# Dist.net
KiCad netlist of a schematic drawn in EAGLE
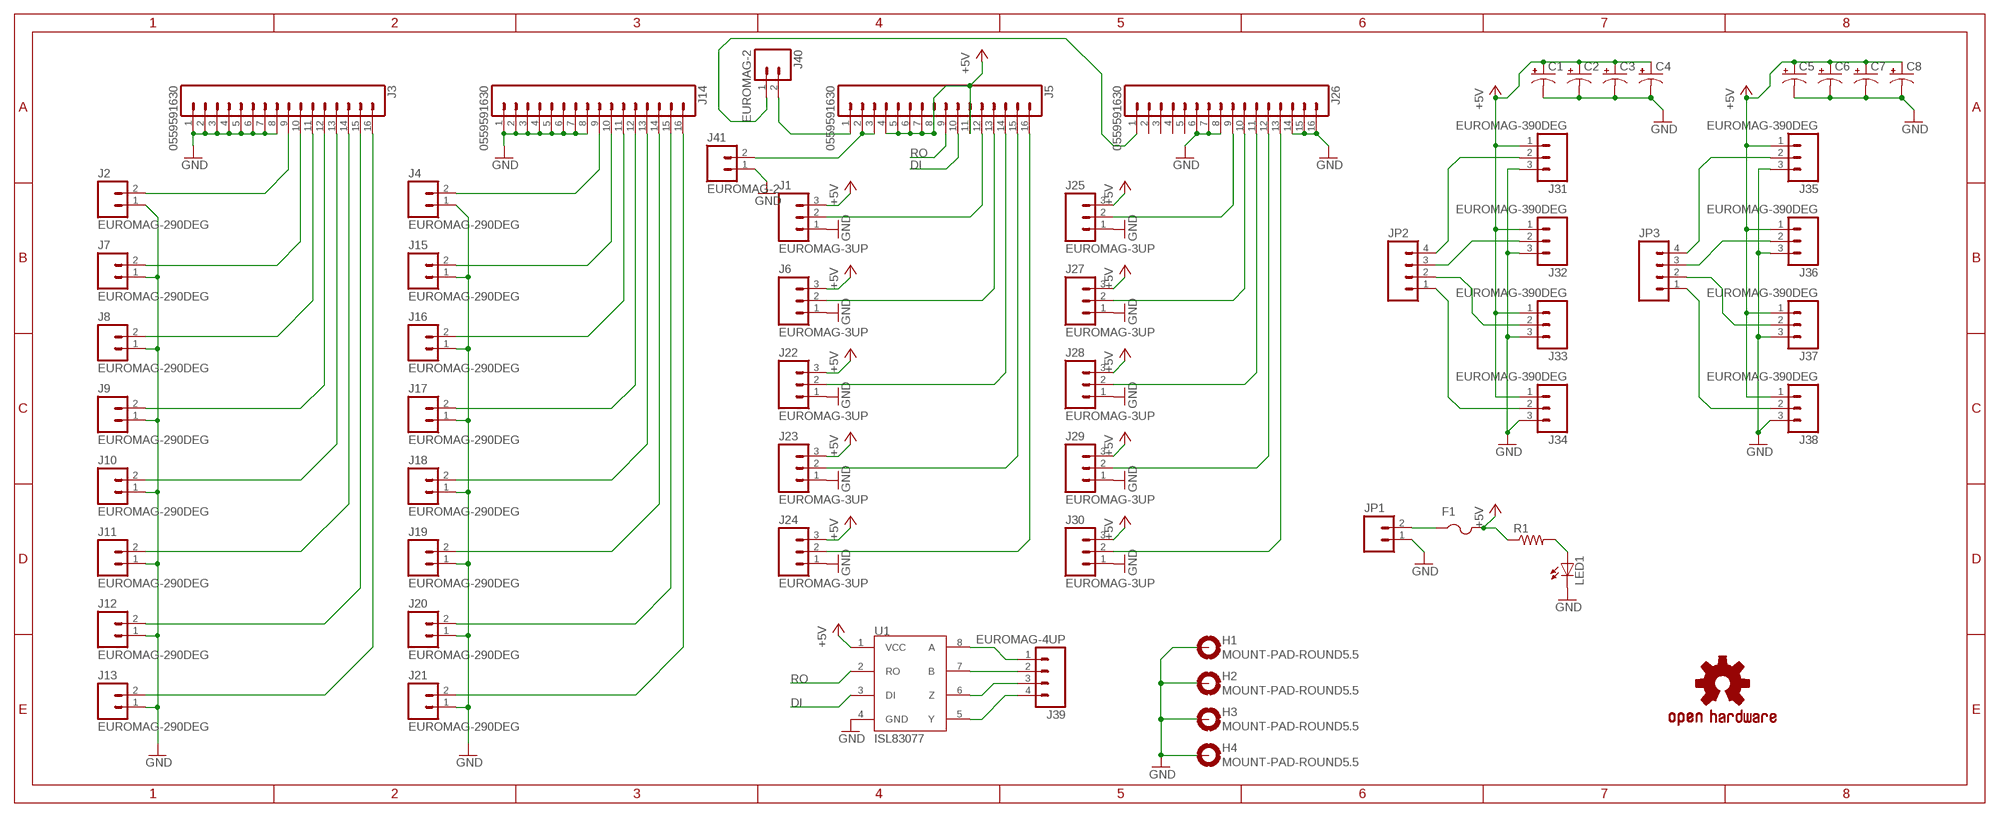
[diagram p0: schematic, sheet 1]

(export (version "E")
  (design (tool "Eeschema 10.0.6"))
  (components
    (comp (ref "C1")
      (value "CAP_POL3528")
      (footprint "eagle-import:EIA3528")
      (libsource (lib "eagle-import") (part "CAP_POL3528"))
    )
    (comp (ref "C2")
      (value "CAP_POL3528")
      (footprint "eagle-import:EIA3528")
      (libsource (lib "eagle-import") (part "CAP_POL3528"))
    )
    (comp (ref "C3")
      (value "CAP_POL3528")
      (footprint "eagle-import:EIA3528")
      (libsource (lib "eagle-import") (part "CAP_POL3528"))
    )
    (comp (ref "C4")
      (value "CAP_POL3528")
      (footprint "eagle-import:EIA3528")
      (libsource (lib "eagle-import") (part "CAP_POL3528"))
    )
    (comp (ref "C5")
      (value "CAP_POL3528")
      (footprint "eagle-import:EIA3528")
      (libsource (lib "eagle-import") (part "CAP_POL3528"))
    )
    (comp (ref "C6")
      (value "CAP_POL3528")
      (footprint "eagle-import:EIA3528")
      (libsource (lib "eagle-import") (part "CAP_POL3528"))
    )
    (comp (ref "C7")
      (value "CAP_POL3528")
      (footprint "eagle-import:EIA3528")
      (libsource (lib "eagle-import") (part "CAP_POL3528"))
    )
    (comp (ref "C8")
      (value "CAP_POL3528")
      (footprint "eagle-import:EIA3528")
      (libsource (lib "eagle-import") (part "CAP_POL3528"))
    )
    (comp (ref "F1")
      (value "PTCFUSE-1812")
      (footprint "eagle-import:1812")
      (libsource (lib "eagle-import") (part "PTCFUSE-1812"))
    )
    (comp (ref "H1")
      (value "MOUNT-PAD-ROUND5.5")
      (footprint "eagle-import:5,5-PAD")
      (libsource (lib "eagle-import") (part "MOUNT-PAD-ROUND5.5"))
    )
    (comp (ref "H2")
      (value "MOUNT-PAD-ROUND5.5")
      (footprint "eagle-import:5,5-PAD")
      (libsource (lib "eagle-import") (part "MOUNT-PAD-ROUND5.5"))
    )
    (comp (ref "H3")
      (value "MOUNT-PAD-ROUND5.5")
      (footprint "eagle-import:5,5-PAD")
      (libsource (lib "eagle-import") (part "MOUNT-PAD-ROUND5.5"))
    )
    (comp (ref "H4")
      (value "MOUNT-PAD-ROUND5.5")
      (footprint "eagle-import:5,5-PAD")
      (libsource (lib "eagle-import") (part "MOUNT-PAD-ROUND5.5"))
    )
    (comp (ref "J1")
      (value "EUROMAG-3UP")
      (footprint "eagle-import:M3-UP")
      (libsource (lib "eagle-import") (part "EUROMAG-3UP"))
    )
    (comp (ref "J2")
      (value "EUROMAG-290DEG")
      (footprint "eagle-import:M2")
      (libsource (lib "eagle-import") (part "EUROMAG-290DEG"))
    )
    (comp (ref "J3")
      (value "0559591630")
      (footprint "eagle-import:0559591630")
      (libsource (lib "eagle-import") (part "0559591630"))
    )
    (comp (ref "J4")
      (value "EUROMAG-290DEG")
      (footprint "eagle-import:M2")
      (libsource (lib "eagle-import") (part "EUROMAG-290DEG"))
    )
    (comp (ref "J5")
      (value "0559591630")
      (footprint "eagle-import:0559591630")
      (libsource (lib "eagle-import") (part "0559591630"))
    )
    (comp (ref "J6")
      (value "EUROMAG-3UP")
      (footprint "eagle-import:M3-UP")
      (libsource (lib "eagle-import") (part "EUROMAG-3UP"))
    )
    (comp (ref "J7")
      (value "EUROMAG-290DEG")
      (footprint "eagle-import:M2")
      (libsource (lib "eagle-import") (part "EUROMAG-290DEG"))
    )
    (comp (ref "J8")
      (value "EUROMAG-290DEG")
      (footprint "eagle-import:M2")
      (libsource (lib "eagle-import") (part "EUROMAG-290DEG"))
    )
    (comp (ref "J9")
      (value "EUROMAG-290DEG")
      (footprint "eagle-import:M2")
      (libsource (lib "eagle-import") (part "EUROMAG-290DEG"))
    )
    (comp (ref "J10")
      (value "EUROMAG-290DEG")
      (footprint "eagle-import:M2")
      (libsource (lib "eagle-import") (part "EUROMAG-290DEG"))
    )
    (comp (ref "J11")
      (value "EUROMAG-290DEG")
      (footprint "eagle-import:M2")
      (libsource (lib "eagle-import") (part "EUROMAG-290DEG"))
    )
    (comp (ref "J12")
      (value "EUROMAG-290DEG")
      (footprint "eagle-import:M2")
      (libsource (lib "eagle-import") (part "EUROMAG-290DEG"))
    )
    (comp (ref "J13")
      (value "EUROMAG-290DEG")
      (footprint "eagle-import:M2")
      (libsource (lib "eagle-import") (part "EUROMAG-290DEG"))
    )
    (comp (ref "J14")
      (value "0559591630")
      (footprint "eagle-import:0559591630")
      (libsource (lib "eagle-import") (part "0559591630"))
    )
    (comp (ref "J15")
      (value "EUROMAG-290DEG")
      (footprint "eagle-import:M2")
      (libsource (lib "eagle-import") (part "EUROMAG-290DEG"))
    )
    (comp (ref "J16")
      (value "EUROMAG-290DEG")
      (footprint "eagle-import:M2")
      (libsource (lib "eagle-import") (part "EUROMAG-290DEG"))
    )
    (comp (ref "J17")
      (value "EUROMAG-290DEG")
      (footprint "eagle-import:M2")
      (libsource (lib "eagle-import") (part "EUROMAG-290DEG"))
    )
    (comp (ref "J18")
      (value "EUROMAG-290DEG")
      (footprint "eagle-import:M2")
      (libsource (lib "eagle-import") (part "EUROMAG-290DEG"))
    )
    (comp (ref "J19")
      (value "EUROMAG-290DEG")
      (footprint "eagle-import:M2")
      (libsource (lib "eagle-import") (part "EUROMAG-290DEG"))
    )
    (comp (ref "J20")
      (value "EUROMAG-290DEG")
      (footprint "eagle-import:M2")
      (libsource (lib "eagle-import") (part "EUROMAG-290DEG"))
    )
    (comp (ref "J21")
      (value "EUROMAG-290DEG")
      (footprint "eagle-import:M2")
      (libsource (lib "eagle-import") (part "EUROMAG-290DEG"))
    )
    (comp (ref "J22")
      (value "EUROMAG-3UP")
      (footprint "eagle-import:M3-UP")
      (libsource (lib "eagle-import") (part "EUROMAG-3UP"))
    )
    (comp (ref "J23")
      (value "EUROMAG-3UP")
      (footprint "eagle-import:M3-UP")
      (libsource (lib "eagle-import") (part "EUROMAG-3UP"))
    )
    (comp (ref "J24")
      (value "EUROMAG-3UP")
      (footprint "eagle-import:M3-UP")
      (libsource (lib "eagle-import") (part "EUROMAG-3UP"))
    )
    (comp (ref "J25")
      (value "EUROMAG-3UP")
      (footprint "eagle-import:M3-UP")
      (libsource (lib "eagle-import") (part "EUROMAG-3UP"))
    )
    (comp (ref "J26")
      (value "0559591630")
      (footprint "eagle-import:0559591630")
      (libsource (lib "eagle-import") (part "0559591630"))
    )
    (comp (ref "J27")
      (value "EUROMAG-3UP")
      (footprint "eagle-import:M3-UP")
      (libsource (lib "eagle-import") (part "EUROMAG-3UP"))
    )
    (comp (ref "J28")
      (value "EUROMAG-3UP")
      (footprint "eagle-import:M3-UP")
      (libsource (lib "eagle-import") (part "EUROMAG-3UP"))
    )
    (comp (ref "J29")
      (value "EUROMAG-3UP")
      (footprint "eagle-import:M3-UP")
      (libsource (lib "eagle-import") (part "EUROMAG-3UP"))
    )
    (comp (ref "J30")
      (value "EUROMAG-3UP")
      (footprint "eagle-import:M3-UP")
      (libsource (lib "eagle-import") (part "EUROMAG-3UP"))
    )
    (comp (ref "J31")
      (value "EUROMAG-390DEG")
      (footprint "eagle-import:M3")
      (libsource (lib "eagle-import") (part "EUROMAG-390DEG"))
    )
    (comp (ref "J32")
      (value "EUROMAG-390DEG")
      (footprint "eagle-import:M3")
      (libsource (lib "eagle-import") (part "EUROMAG-390DEG"))
    )
    (comp (ref "J33")
      (value "EUROMAG-390DEG")
      (footprint "eagle-import:M3")
      (libsource (lib "eagle-import") (part "EUROMAG-390DEG"))
    )
    (comp (ref "J34")
      (value "EUROMAG-390DEG")
      (footprint "eagle-import:M3")
      (libsource (lib "eagle-import") (part "EUROMAG-390DEG"))
    )
    (comp (ref "J35")
      (value "EUROMAG-390DEG")
      (footprint "eagle-import:M3")
      (libsource (lib "eagle-import") (part "EUROMAG-390DEG"))
    )
    (comp (ref "J36")
      (value "EUROMAG-390DEG")
      (footprint "eagle-import:M3")
      (libsource (lib "eagle-import") (part "EUROMAG-390DEG"))
    )
    (comp (ref "J37")
      (value "EUROMAG-390DEG")
      (footprint "eagle-import:M3")
      (libsource (lib "eagle-import") (part "EUROMAG-390DEG"))
    )
    (comp (ref "J38")
      (value "EUROMAG-390DEG")
      (footprint "eagle-import:M3")
      (libsource (lib "eagle-import") (part "EUROMAG-390DEG"))
    )
    (comp (ref "J39")
      (value "EUROMAG-4UP")
      (footprint "eagle-import:M4-90")
      (libsource (lib "eagle-import") (part "EUROMAG-4UP"))
    )
    (comp (ref "J40")
      (value "EUROMAG-2")
      (footprint "eagle-import:M2-UP")
      (libsource (lib "eagle-import") (part "EUROMAG-2"))
    )
    (comp (ref "J41")
      (value "EUROMAG-2")
      (footprint "eagle-import:M2-UP")
      (libsource (lib "eagle-import") (part "EUROMAG-2"))
    )
    (comp (ref "JP1")
      (value "M02POLAR_LOCK")
      (footprint "eagle-import:MOLEX-1X2_LOCK")
      (libsource (lib "eagle-import") (part "M02POLAR_LOCK"))
    )
    (comp (ref "JP2")
      (value "M04POLAR_LOCK")
      (footprint "eagle-import:MOLEX-1X4_LOCK")
      (libsource (lib "eagle-import") (part "M04POLAR_LOCK"))
    )
    (comp (ref "JP3")
      (value "M04POLAR_LOCK")
      (footprint "eagle-import:MOLEX-1X4_LOCK")
      (libsource (lib "eagle-import") (part "M04POLAR_LOCK"))
    )
    (comp (ref "LED1")
      (value "LEDCHIPLED_0805")
      (footprint "eagle-import:CHIPLED_0805")
      (libsource (lib "eagle-import") (part "LEDCHIPLED_0805"))
    )
    (comp (ref "R1")
      (value "R-US_R0805")
      (footprint "eagle-import:R0805")
      (libsource (lib "eagle-import") (part "R-US_R0805"))
    )
    (comp (ref "U$1")
      (value "OSHW-LOGOL")
      (footprint "eagle-import:OSHW-LOGO-L")
      (libsource (lib "eagle-import") (part "OSHW-LOGOL"))
    )
    (comp (ref "U1")
      (value "ISL83077")
      (footprint "eagle-import:SO08")
      (libsource (lib "eagle-import") (part "ISL83077"))
    )
  )
  (nets
    (net (code "1") (name "+5V") (class "Default")
      (node (ref "C1") (pin "A") (pinfunction "+_A") (pintype "passive"))
      (node (ref "C2") (pin "A") (pinfunction "+_A") (pintype "passive"))
      (node (ref "C3") (pin "A") (pinfunction "+_A") (pintype "passive"))
      (node (ref "C4") (pin "A") (pinfunction "+_A") (pintype "passive"))
      (node (ref "C5") (pin "A") (pinfunction "+_A") (pintype "passive"))
      (node (ref "C6") (pin "A") (pinfunction "+_A") (pintype "passive"))
      (node (ref "C7") (pin "A") (pinfunction "+_A") (pintype "passive"))
      (node (ref "C8") (pin "A") (pinfunction "+_A") (pintype "passive"))
      (node (ref "F1") (pin "2") (pinfunction "2_2") (pintype "passive"))
      (node (ref "J1") (pin "3") (pinfunction "3_3") (pintype "passive"))
      (node (ref "J22") (pin "3") (pinfunction "3_3") (pintype "passive"))
      (node (ref "J23") (pin "3") (pinfunction "3_3") (pintype "passive"))
      (node (ref "J24") (pin "3") (pinfunction "3_3") (pintype "passive"))
      (node (ref "J25") (pin "3") (pinfunction "3_3") (pintype "passive"))
      (node (ref "J27") (pin "3") (pinfunction "3_3") (pintype "passive"))
      (node (ref "J28") (pin "3") (pinfunction "3_3") (pintype "passive"))
      (node (ref "J29") (pin "3") (pinfunction "3_3") (pintype "passive"))
      (node (ref "J30") (pin "3") (pinfunction "3_3") (pintype "passive"))
      (node (ref "J31") (pin "1") (pinfunction "1_1") (pintype "passive"))
      (node (ref "J32") (pin "1") (pinfunction "1_1") (pintype "passive"))
      (node (ref "J33") (pin "1") (pinfunction "1_1") (pintype "passive"))
      (node (ref "J34") (pin "1") (pinfunction "1_1") (pintype "passive"))
      (node (ref "J35") (pin "1") (pinfunction "1_1") (pintype "passive"))
      (node (ref "J36") (pin "1") (pinfunction "1_1") (pintype "passive"))
      (node (ref "J37") (pin "1") (pinfunction "1_1") (pintype "passive"))
      (node (ref "J38") (pin "1") (pinfunction "1_1") (pintype "passive"))
      (node (ref "J5") (pin "11") (pinfunction "11_11") (pintype "passive"))
      (node (ref "J5") (pin "4") (pinfunction "4_4") (pintype "passive"))
      (node (ref "J5") (pin "5") (pinfunction "5_5") (pintype "passive"))
      (node (ref "J5") (pin "6") (pinfunction "6_6") (pintype "passive"))
      (node (ref "J5") (pin "7") (pinfunction "7_7") (pintype "passive"))
      (node (ref "J5") (pin "8") (pinfunction "8_8") (pintype "passive"))
      (node (ref "J6") (pin "3") (pinfunction "3_3") (pintype "passive"))
      (node (ref "R1") (pin "1") (pinfunction "1_1") (pintype "passive"))
      (node (ref "U1") (pin "1") (pinfunction "VCC_1") (pintype "bidirectional"))
    )
    (net (code "2") (name "/DI") (class "Default")
      (node (ref "J5") (pin "10") (pinfunction "10_10") (pintype "passive"))
      (node (ref "U1") (pin "3") (pinfunction "DI_3") (pintype "bidirectional"))
    )
    (net (code "3") (name "/RO") (class "Default")
      (node (ref "J5") (pin "9") (pinfunction "9_9") (pintype "passive"))
      (node (ref "U1") (pin "2") (pinfunction "RO_2") (pintype "bidirectional"))
    )
    (net (code "4") (name "GND") (class "Default")
      (node (ref "C1") (pin "C") (pinfunction "-_C") (pintype "passive"))
      (node (ref "C2") (pin "C") (pinfunction "-_C") (pintype "passive"))
      (node (ref "C3") (pin "C") (pinfunction "-_C") (pintype "passive"))
      (node (ref "C4") (pin "C") (pinfunction "-_C") (pintype "passive"))
      (node (ref "C5") (pin "C") (pinfunction "-_C") (pintype "passive"))
      (node (ref "C6") (pin "C") (pinfunction "-_C") (pintype "passive"))
      (node (ref "C7") (pin "C") (pinfunction "-_C") (pintype "passive"))
      (node (ref "C8") (pin "C") (pinfunction "-_C") (pintype "passive"))
      (node (ref "H1") (pin "B5,5") (pinfunction "MOUNT_B5,5") (pintype "passive"))
      (node (ref "H2") (pin "B5,5") (pinfunction "MOUNT_B5,5") (pintype "passive"))
      (node (ref "H3") (pin "B5,5") (pinfunction "MOUNT_B5,5") (pintype "passive"))
      (node (ref "H4") (pin "B5,5") (pinfunction "MOUNT_B5,5") (pintype "passive"))
      (node (ref "J1") (pin "1") (pinfunction "1_1") (pintype "passive"))
      (node (ref "J10") (pin "1") (pinfunction "1_1") (pintype "passive"))
      (node (ref "J11") (pin "1") (pinfunction "1_1") (pintype "passive"))
      (node (ref "J12") (pin "1") (pinfunction "1_1") (pintype "passive"))
      (node (ref "J13") (pin "1") (pinfunction "1_1") (pintype "passive"))
      (node (ref "J14") (pin "1") (pinfunction "1_1") (pintype "passive"))
      (node (ref "J14") (pin "2") (pinfunction "2_2") (pintype "passive"))
      (node (ref "J14") (pin "3") (pinfunction "3_3") (pintype "passive"))
      (node (ref "J14") (pin "4") (pinfunction "4_4") (pintype "passive"))
      (node (ref "J14") (pin "5") (pinfunction "5_5") (pintype "passive"))
      (node (ref "J14") (pin "6") (pinfunction "6_6") (pintype "passive"))
      (node (ref "J14") (pin "7") (pinfunction "7_7") (pintype "passive"))
      (node (ref "J14") (pin "8") (pinfunction "8_8") (pintype "passive"))
      (node (ref "J15") (pin "1") (pinfunction "1_1") (pintype "passive"))
      (node (ref "J16") (pin "1") (pinfunction "1_1") (pintype "passive"))
      (node (ref "J17") (pin "1") (pinfunction "1_1") (pintype "passive"))
      (node (ref "J18") (pin "1") (pinfunction "1_1") (pintype "passive"))
      (node (ref "J19") (pin "1") (pinfunction "1_1") (pintype "passive"))
      (node (ref "J2") (pin "1") (pinfunction "1_1") (pintype "passive"))
      (node (ref "J20") (pin "1") (pinfunction "1_1") (pintype "passive"))
      (node (ref "J21") (pin "1") (pinfunction "1_1") (pintype "passive"))
      (node (ref "J22") (pin "1") (pinfunction "1_1") (pintype "passive"))
      (node (ref "J23") (pin "1") (pinfunction "1_1") (pintype "passive"))
      (node (ref "J24") (pin "1") (pinfunction "1_1") (pintype "passive"))
      (node (ref "J25") (pin "1") (pinfunction "1_1") (pintype "passive"))
      (node (ref "J26") (pin "14") (pinfunction "14_14") (pintype "passive"))
      (node (ref "J26") (pin "15") (pinfunction "15_15") (pintype "passive"))
      (node (ref "J26") (pin "16") (pinfunction "16_16") (pintype "passive"))
      (node (ref "J26") (pin "6") (pinfunction "6_6") (pintype "passive"))
      (node (ref "J26") (pin "7") (pinfunction "7_7") (pintype "passive"))
      (node (ref "J26") (pin "8") (pinfunction "8_8") (pintype "passive"))
      (node (ref "J27") (pin "1") (pinfunction "1_1") (pintype "passive"))
      (node (ref "J28") (pin "1") (pinfunction "1_1") (pintype "passive"))
      (node (ref "J29") (pin "1") (pinfunction "1_1") (pintype "passive"))
      (node (ref "J3") (pin "1") (pinfunction "1_1") (pintype "passive"))
      (node (ref "J3") (pin "2") (pinfunction "2_2") (pintype "passive"))
      (node (ref "J3") (pin "3") (pinfunction "3_3") (pintype "passive"))
      (node (ref "J3") (pin "4") (pinfunction "4_4") (pintype "passive"))
      (node (ref "J3") (pin "5") (pinfunction "5_5") (pintype "passive"))
      (node (ref "J3") (pin "6") (pinfunction "6_6") (pintype "passive"))
      (node (ref "J3") (pin "7") (pinfunction "7_7") (pintype "passive"))
      (node (ref "J3") (pin "8") (pinfunction "8_8") (pintype "passive"))
      (node (ref "J30") (pin "1") (pinfunction "1_1") (pintype "passive"))
      (node (ref "J31") (pin "3") (pinfunction "3_3") (pintype "passive"))
      (node (ref "J32") (pin "3") (pinfunction "3_3") (pintype "passive"))
      (node (ref "J33") (pin "3") (pinfunction "3_3") (pintype "passive"))
      (node (ref "J34") (pin "3") (pinfunction "3_3") (pintype "passive"))
      (node (ref "J35") (pin "3") (pinfunction "3_3") (pintype "passive"))
      (node (ref "J36") (pin "3") (pinfunction "3_3") (pintype "passive"))
      (node (ref "J37") (pin "3") (pinfunction "3_3") (pintype "passive"))
      (node (ref "J38") (pin "3") (pinfunction "3_3") (pintype "passive"))
      (node (ref "J4") (pin "1") (pinfunction "1_1") (pintype "passive"))
      (node (ref "J41") (pin "1") (pinfunction "1_1") (pintype "passive"))
      (node (ref "J6") (pin "1") (pinfunction "1_1") (pintype "passive"))
      (node (ref "J7") (pin "1") (pinfunction "1_1") (pintype "passive"))
      (node (ref "J8") (pin "1") (pinfunction "1_1") (pintype "passive"))
      (node (ref "J9") (pin "1") (pinfunction "1_1") (pintype "passive"))
      (node (ref "JP1") (pin "1") (pinfunction "1_1") (pintype "passive"))
      (node (ref "LED1") (pin "C") (pinfunction "C_C") (pintype "passive"))
      (node (ref "U1") (pin "4") (pinfunction "GND_4") (pintype "bidirectional"))
    )
    (net (code "5") (name "Net-(F1-Pad1)") (class "Default")
      (node (ref "F1") (pin "1") (pinfunction "1_1") (pintype "passive"))
      (node (ref "JP1") (pin "2") (pinfunction "2_2") (pintype "passive"))
    )
    (net (code "6") (name "Net-(J1-Pad2)") (class "Default")
      (node (ref "J1") (pin "2") (pinfunction "2_2") (pintype "passive"))
      (node (ref "J5") (pin "12") (pinfunction "12_12") (pintype "passive"))
    )
    (net (code "7") (name "Net-(J2-Pad2)") (class "Default")
      (node (ref "J2") (pin "2") (pinfunction "2_2") (pintype "passive"))
      (node (ref "J3") (pin "9") (pinfunction "9_9") (pintype "passive"))
    )
    (net (code "8") (name "Net-(J3-Pad10)") (class "Default")
      (node (ref "J3") (pin "10") (pinfunction "10_10") (pintype "passive"))
      (node (ref "J7") (pin "2") (pinfunction "2_2") (pintype "passive"))
    )
    (net (code "9") (name "Net-(J3-Pad11)") (class "Default")
      (node (ref "J3") (pin "11") (pinfunction "11_11") (pintype "passive"))
      (node (ref "J8") (pin "2") (pinfunction "2_2") (pintype "passive"))
    )
    (net (code "10") (name "Net-(J3-Pad12)") (class "Default")
      (node (ref "J3") (pin "12") (pinfunction "12_12") (pintype "passive"))
      (node (ref "J9") (pin "2") (pinfunction "2_2") (pintype "passive"))
    )
    (net (code "11") (name "Net-(J5-Pad13)") (class "Default")
      (node (ref "J5") (pin "13") (pinfunction "13_13") (pintype "passive"))
      (node (ref "J6") (pin "2") (pinfunction "2_2") (pintype "passive"))
    )
    (net (code "12") (name "Net-(J10-Pad2)") (class "Default")
      (node (ref "J10") (pin "2") (pinfunction "2_2") (pintype "passive"))
      (node (ref "J3") (pin "13") (pinfunction "13_13") (pintype "passive"))
    )
    (net (code "13") (name "Net-(J11-Pad2)") (class "Default")
      (node (ref "J11") (pin "2") (pinfunction "2_2") (pintype "passive"))
      (node (ref "J3") (pin "14") (pinfunction "14_14") (pintype "passive"))
    )
    (net (code "14") (name "Net-(J12-Pad2)") (class "Default")
      (node (ref "J12") (pin "2") (pinfunction "2_2") (pintype "passive"))
      (node (ref "J3") (pin "15") (pinfunction "15_15") (pintype "passive"))
    )
    (net (code "15") (name "Net-(J13-Pad2)") (class "Default")
      (node (ref "J13") (pin "2") (pinfunction "2_2") (pintype "passive"))
      (node (ref "J3") (pin "16") (pinfunction "16_16") (pintype "passive"))
    )
    (net (code "16") (name "Net-(J14-Pad9)") (class "Default")
      (node (ref "J14") (pin "9") (pinfunction "9_9") (pintype "passive"))
      (node (ref "J4") (pin "2") (pinfunction "2_2") (pintype "passive"))
    )
    (net (code "17") (name "Net-(J14-Pad10)") (class "Default")
      (node (ref "J14") (pin "10") (pinfunction "10_10") (pintype "passive"))
      (node (ref "J15") (pin "2") (pinfunction "2_2") (pintype "passive"))
    )
    (net (code "18") (name "Net-(J14-Pad11)") (class "Default")
      (node (ref "J14") (pin "11") (pinfunction "11_11") (pintype "passive"))
      (node (ref "J16") (pin "2") (pinfunction "2_2") (pintype "passive"))
    )
    (net (code "19") (name "Net-(J14-Pad12)") (class "Default")
      (node (ref "J14") (pin "12") (pinfunction "12_12") (pintype "passive"))
      (node (ref "J17") (pin "2") (pinfunction "2_2") (pintype "passive"))
    )
    (net (code "20") (name "Net-(J14-Pad13)") (class "Default")
      (node (ref "J14") (pin "13") (pinfunction "13_13") (pintype "passive"))
      (node (ref "J18") (pin "2") (pinfunction "2_2") (pintype "passive"))
    )
    (net (code "21") (name "Net-(J14-Pad14)") (class "Default")
      (node (ref "J14") (pin "14") (pinfunction "14_14") (pintype "passive"))
      (node (ref "J19") (pin "2") (pinfunction "2_2") (pintype "passive"))
    )
    (net (code "22") (name "Net-(J14-Pad15)") (class "Default")
      (node (ref "J14") (pin "15") (pinfunction "15_15") (pintype "passive"))
      (node (ref "J20") (pin "2") (pinfunction "2_2") (pintype "passive"))
    )
    (net (code "23") (name "Net-(J14-Pad16)") (class "Default")
      (node (ref "J14") (pin "16") (pinfunction "16_16") (pintype "passive"))
      (node (ref "J21") (pin "2") (pinfunction "2_2") (pintype "passive"))
    )
    (net (code "24") (name "Net-(J22-Pad2)") (class "Default")
      (node (ref "J22") (pin "2") (pinfunction "2_2") (pintype "passive"))
      (node (ref "J5") (pin "14") (pinfunction "14_14") (pintype "passive"))
    )
    (net (code "25") (name "Net-(J23-Pad2)") (class "Default")
      (node (ref "J23") (pin "2") (pinfunction "2_2") (pintype "passive"))
      (node (ref "J5") (pin "15") (pinfunction "15_15") (pintype "passive"))
    )
    (net (code "26") (name "Net-(J24-Pad2)") (class "Default")
      (node (ref "J24") (pin "2") (pinfunction "2_2") (pintype "passive"))
      (node (ref "J5") (pin "16") (pinfunction "16_16") (pintype "passive"))
    )
    (net (code "27") (name "Net-(J25-Pad2)") (class "Default")
      (node (ref "J25") (pin "2") (pinfunction "2_2") (pintype "passive"))
      (node (ref "J26") (pin "9") (pinfunction "9_9") (pintype "passive"))
    )
    (net (code "28") (name "Net-(J26-Pad1)") (class "Default")
      (node (ref "J26") (pin "1") (pinfunction "1_1") (pintype "passive"))
      (node (ref "J40") (pin "1") (pinfunction "1_1") (pintype "passive"))
    )
    (net (code "29") (name "Net-(J26-Pad10)") (class "Default")
      (node (ref "J26") (pin "10") (pinfunction "10_10") (pintype "passive"))
      (node (ref "J27") (pin "2") (pinfunction "2_2") (pintype "passive"))
    )
    (net (code "30") (name "Net-(J26-Pad11)") (class "Default")
      (node (ref "J26") (pin "11") (pinfunction "11_11") (pintype "passive"))
      (node (ref "J28") (pin "2") (pinfunction "2_2") (pintype "passive"))
    )
    (net (code "31") (name "Net-(J26-Pad12)") (class "Default")
      (node (ref "J26") (pin "12") (pinfunction "12_12") (pintype "passive"))
      (node (ref "J29") (pin "2") (pinfunction "2_2") (pintype "passive"))
    )
    (net (code "32") (name "Net-(J26-Pad13)") (class "Default")
      (node (ref "J26") (pin "13") (pinfunction "13_13") (pintype "passive"))
      (node (ref "J30") (pin "2") (pinfunction "2_2") (pintype "passive"))
    )
    (net (code "33") (name "Net-(J31-Pad2)") (class "Default")
      (node (ref "J31") (pin "2") (pinfunction "2_2") (pintype "passive"))
      (node (ref "JP2") (pin "4") (pinfunction "4_4") (pintype "passive"))
    )
    (net (code "34") (name "Net-(J32-Pad2)") (class "Default")
      (node (ref "J32") (pin "2") (pinfunction "2_2") (pintype "passive"))
      (node (ref "JP2") (pin "3") (pinfunction "3_3") (pintype "passive"))
    )
    (net (code "35") (name "Net-(J33-Pad2)") (class "Default")
      (node (ref "J33") (pin "2") (pinfunction "2_2") (pintype "passive"))
      (node (ref "JP2") (pin "2") (pinfunction "2_2") (pintype "passive"))
    )
    (net (code "36") (name "Net-(J34-Pad2)") (class "Default")
      (node (ref "J34") (pin "2") (pinfunction "2_2") (pintype "passive"))
      (node (ref "JP2") (pin "1") (pinfunction "1_1") (pintype "passive"))
    )
    (net (code "37") (name "Net-(J35-Pad2)") (class "Default")
      (node (ref "J35") (pin "2") (pinfunction "2_2") (pintype "passive"))
      (node (ref "JP3") (pin "4") (pinfunction "4_4") (pintype "passive"))
    )
    (net (code "38") (name "Net-(J36-Pad2)") (class "Default")
      (node (ref "J36") (pin "2") (pinfunction "2_2") (pintype "passive"))
      (node (ref "JP3") (pin "3") (pinfunction "3_3") (pintype "passive"))
    )
    (net (code "39") (name "Net-(J37-Pad2)") (class "Default")
      (node (ref "J37") (pin "2") (pinfunction "2_2") (pintype "passive"))
      (node (ref "JP3") (pin "2") (pinfunction "2_2") (pintype "passive"))
    )
    (net (code "40") (name "Net-(J38-Pad2)") (class "Default")
      (node (ref "J38") (pin "2") (pinfunction "2_2") (pintype "passive"))
      (node (ref "JP3") (pin "1") (pinfunction "1_1") (pintype "passive"))
    )
    (net (code "41") (name "Net-(J40-Pad2)") (class "Default")
      (node (ref "J40") (pin "2") (pinfunction "2_2") (pintype "passive"))
      (node (ref "J5") (pin "1") (pinfunction "1_1") (pintype "passive"))
    )
    (net (code "42") (name "Net-(J41-Pad2)") (class "Default")
      (node (ref "J41") (pin "2") (pinfunction "2_2") (pintype "passive"))
      (node (ref "J5") (pin "2") (pinfunction "2_2") (pintype "passive"))
      (node (ref "J5") (pin "3") (pinfunction "3_3") (pintype "passive"))
    )
    (net (code "43") (name "Net-(LED1-PadA)") (class "Default")
      (node (ref "LED1") (pin "A") (pinfunction "A_A") (pintype "passive"))
      (node (ref "R1") (pin "2") (pinfunction "2_2") (pintype "passive"))
    )
    (net (code "44") (name "Net-(U1-A)") (class "Default")
      (node (ref "J39") (pin "1") (pinfunction "1_1") (pintype "passive"))
      (node (ref "U1") (pin "8") (pinfunction "A_8") (pintype "bidirectional"))
    )
    (net (code "45") (name "Net-(U1-B)") (class "Default")
      (node (ref "J39") (pin "2") (pinfunction "2_2") (pintype "passive"))
      (node (ref "U1") (pin "7") (pinfunction "B_7") (pintype "bidirectional"))
    )
    (net (code "46") (name "Net-(U1-Y)") (class "Default")
      (node (ref "J39") (pin "4") (pinfunction "4_4") (pintype "passive"))
      (node (ref "U1") (pin "5") (pinfunction "Y_5") (pintype "bidirectional"))
    )
    (net (code "47") (name "Net-(U1-Z)") (class "Default")
      (node (ref "J39") (pin "3") (pinfunction "3_3") (pintype "passive"))
      (node (ref "U1") (pin "6") (pinfunction "Z_6") (pintype "bidirectional"))
    )
    (net (code "48") (name "unconnected-(J26-Pad2)") (class "Default")
      (node (ref "J26") (pin "2") (pinfunction "2_2") (pintype "passive"))
    )
    (net (code "49") (name "unconnected-(J26-Pad3)") (class "Default")
      (node (ref "J26") (pin "3") (pinfunction "3_3") (pintype "passive"))
    )
    (net (code "50") (name "unconnected-(J26-Pad4)") (class "Default")
      (node (ref "J26") (pin "4") (pinfunction "4_4") (pintype "passive"))
    )
    (net (code "51") (name "unconnected-(J26-Pad5)") (class "Default")
      (node (ref "J26") (pin "5") (pinfunction "5_5") (pintype "passive"))
    )
  )
)
